# DAPLINK_STLINK_V2-1.net
KiCad netlist of a schematic drawn in Altium Designer
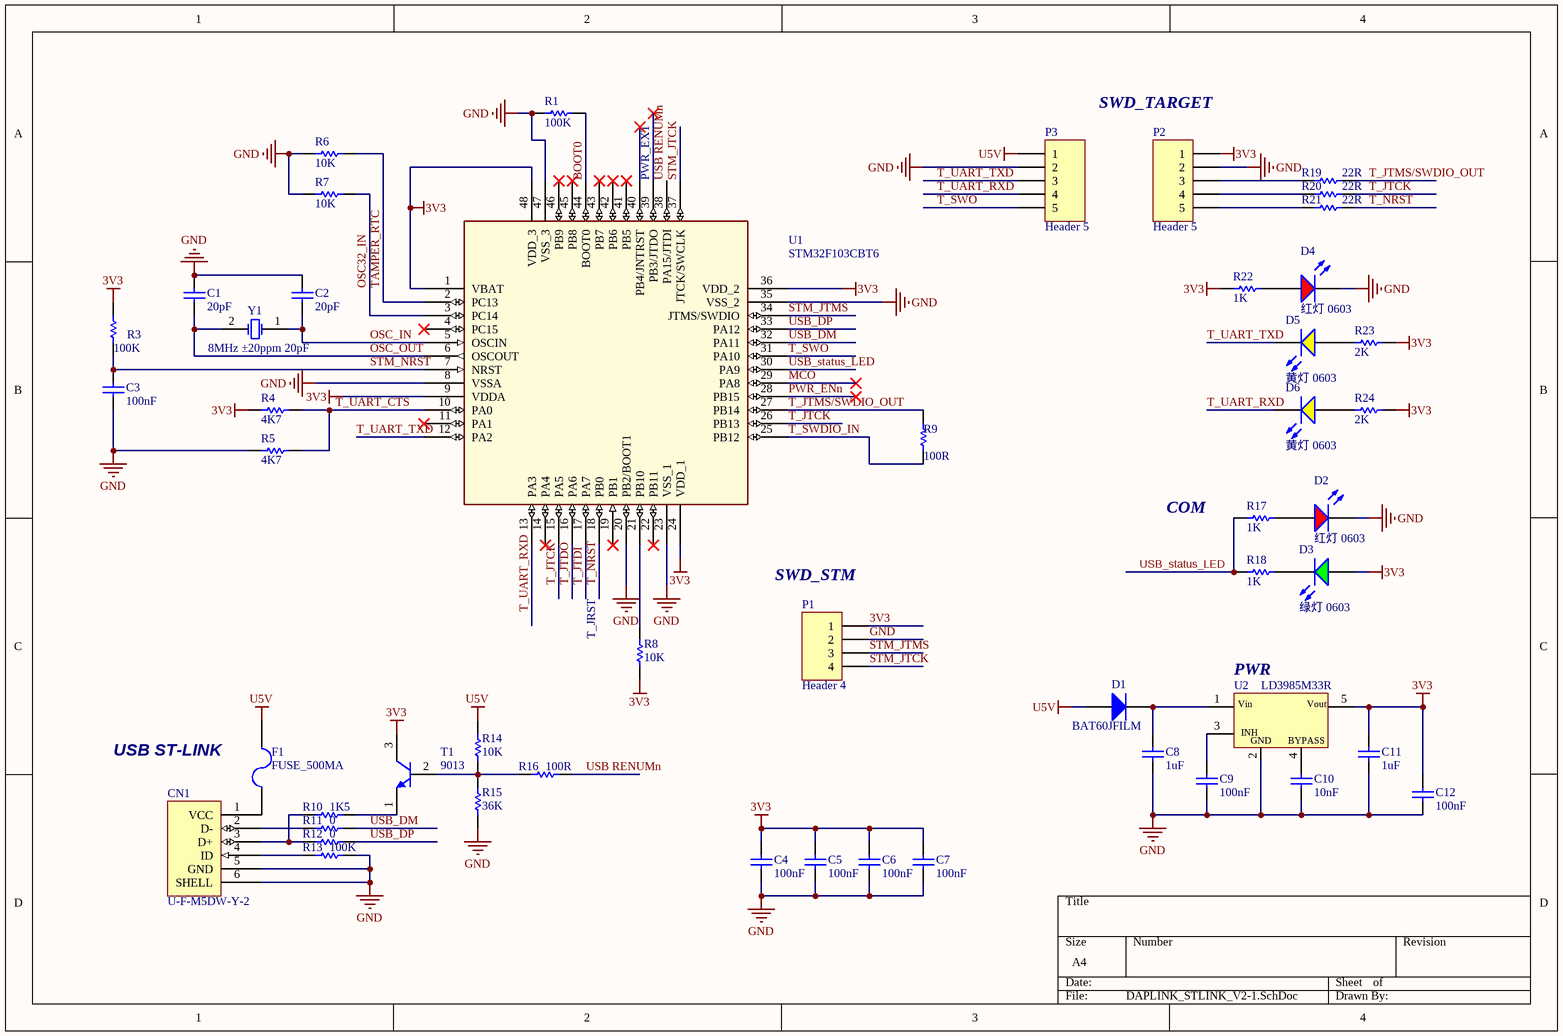
[diagram p0: DAPLINK_STLINK_V2-1.SchDoc]

(export (version "E")
  (design (tool "Eeschema 10.0.6"))
  (components
    (comp (ref "C1")
      (value "20pF")
      (footprint "0603_C")
      (description "Capacitor  0603 20pF")
      (fields (field (name "PUBLISHER") "Altium Limited"))
      (libsource (lib "Miscellaneous Devices") (part "Cap"))
    )
    (comp (ref "C2")
      (value "20pF")
      (footprint "0603_C")
      (description "Capacitor  0603 20pF")
      (fields (field (name "PUBLISHER") "Altium Limited"))
      (libsource (lib "Miscellaneous Devices") (part "Cap"))
    )
    (comp (ref "C3")
      (value "100nF")
      (footprint "0603_C")
      (description "Capacitor  0603 100nF")
      (fields (field (name "PUBLISHER") "Altium Limited"))
      (libsource (lib "Miscellaneous Devices") (part "Cap"))
    )
    (comp (ref "C4")
      (value "100nF")
      (footprint "0603_C")
      (description "Capacitor  0603  100nF")
      (fields (field (name "PUBLISHER") "Altium Limited"))
      (libsource (lib "Miscellaneous Devices") (part "Cap"))
    )
    (comp (ref "C5")
      (value "100nF")
      (footprint "0603_C")
      (description "Capacitor  0603  100nF")
      (fields (field (name "PUBLISHER") "Altium Limited"))
      (libsource (lib "Miscellaneous Devices") (part "Cap"))
    )
    (comp (ref "C6")
      (value "100nF")
      (footprint "0603_C")
      (description "Capacitor 0603 100nF")
      (fields (field (name "PUBLISHER") "Altium Limited"))
      (libsource (lib "Miscellaneous Devices") (part "Cap"))
    )
    (comp (ref "C7")
      (value "100nF")
      (footprint "0603_C")
      (description "Capacitor 0603 100nF")
      (fields (field (name "PUBLISHER") "Altium Limited"))
      (libsource (lib "Miscellaneous Devices") (part "Cap"))
    )
    (comp (ref "C8")
      (value "1uF")
      (footprint "0603_C")
      (description "Capacitor 0603 1uF")
      (fields (field (name "PUBLISHER") "Altium Limited"))
      (libsource (lib "Miscellaneous Devices") (part "Cap"))
    )
    (comp (ref "C9")
      (value "100nF")
      (footprint "0603_C")
      (description "Capacitor 0603 100nF")
      (fields (field (name "PUBLISHER") "Altium Limited"))
      (libsource (lib "Miscellaneous Devices") (part "Cap"))
    )
    (comp (ref "C10")
      (value "10nF")
      (footprint "0603_C")
      (description "Capacitor  0603  10nF")
      (fields (field (name "PUBLISHER") "Altium Limited"))
      (libsource (lib "Miscellaneous Devices") (part "Cap"))
    )
    (comp (ref "C11")
      (value "1uF")
      (footprint "0603_C")
      (description "Capacitor 0603 1uF")
      (fields (field (name "PUBLISHER") "Altium Limited"))
      (libsource (lib "Miscellaneous Devices") (part "Cap"))
    )
    (comp (ref "C12")
      (value "100nF")
      (footprint "0603_C")
      (description "Capacitor  0603  100nF")
      (fields (field (name "PUBLISHER") "Altium Limited"))
      (libsource (lib "Miscellaneous Devices") (part "Cap"))
    )
    (comp (ref "CN1")
      (value "U-F-M5DW-Y-2")
      (footprint "MICRO-USB")
      (description "USB-Micro-typeB connector")
      (libsource (lib "STLINK") (part "USB-MICRO-typeB connector_1"))
    )
    (comp (ref "D1")
      (value "BAT60JFILM")
      (footprint "SOD-323")
      (libsource (lib "STLINK") (part "BAT60JFILM"))
    )
    (comp (ref "D2")
      (value "红灯 0603")
      (footprint "0603_LED_S1")
      (description "发光二极管")
      (libsource (lib "Miscellaneous Devices LC") (part "0603 红灯"))
    )
    (comp (ref "D3")
      (value "绿灯 0603")
      (footprint "0603_LED_S1")
      (description "发光二极管")
      (libsource (lib "Miscellaneous Devices LC") (part "0603 绿灯"))
    )
    (comp (ref "D4")
      (value "红灯 0603")
      (footprint "0603_LED_S1")
      (description "发光二极管")
      (libsource (lib "Miscellaneous Devices LC") (part "0603 红灯"))
    )
    (comp (ref "D5")
      (value "黄灯 0603")
      (footprint "0603_LED_S1")
      (description "发光二极管")
      (libsource (lib "Miscellaneous Devices LC") (part "0603 黄灯"))
    )
    (comp (ref "D6")
      (value "黄灯 0603")
      (footprint "0603_LED_S1")
      (description "发光二极管")
      (libsource (lib "Miscellaneous Devices LC") (part "0603 黄灯"))
    )
    (comp (ref "F1")
      (value "FUSE_500MA")
      (footprint "1206_C")
      (description "自恢复保险丝_SMD1206_500ma")
      (fields (field (name "PUBLISHER") "Altium Limited"))
      (libsource (lib "Miscellaneous Devices") (part "Fuse 2"))
    )
    (comp (ref "P1")
      (value "Header 4")
      (footprint "HDR1X4")
      (description "Header, 4-Pin")
      (fields (field (name "PUBLISHER") "Altium Limited"))
      (libsource (lib "Miscellaneous Connectors") (part "Header 4"))
    )
    (comp (ref "P2")
      (value "Header 5")
      (footprint "HDR2.54-M-WS-5P-2D")
      (description "Header, 5-Pin")
      (fields (field (name "PUBLISHER") "Altium Limited"))
      (libsource (lib "Miscellaneous Connectors") (part "Header 5"))
    )
    (comp (ref "P3")
      (value "Header 5")
      (footprint "HDR2.54-M-WS-5P-2D")
      (description "Header, 5-Pin")
      (fields (field (name "PUBLISHER") "Altium Limited"))
      (libsource (lib "") (part "Header 5_1"))
    )
    (comp (ref "R1")
      (value "100K")
      (footprint "0603_C")
      (description "Resistor 0603")
      (libsource (lib "Miscellaneous Devices") (part "Res1"))
    )
    (comp (ref "R3")
      (value "100K")
      (footprint "0603_C")
      (description "Resistor  0603")
      (libsource (lib "Miscellaneous Devices") (part "Res1"))
    )
    (comp (ref "R4")
      (value "4K7")
      (footprint "0603_C")
      (description "Resistor  0603")
      (libsource (lib "Miscellaneous Devices") (part "Res1"))
    )
    (comp (ref "R5")
      (value "4K7")
      (footprint "0603_C")
      (description "Resistor  0603")
      (libsource (lib "Miscellaneous Devices") (part "Res1"))
    )
    (comp (ref "R6")
      (value "10K")
      (footprint "0603_C")
      (description "Resistor  0603")
      (libsource (lib "Miscellaneous Devices") (part "Res1"))
    )
    (comp (ref "R7")
      (value "10K")
      (footprint "0603_C")
      (description "Resistor  0603")
      (libsource (lib "Miscellaneous Devices") (part "Res1"))
    )
    (comp (ref "R8")
      (value "10K")
      (footprint "0603_C")
      (description "Resistor  0603")
      (libsource (lib "Miscellaneous Devices") (part "Res1"))
    )
    (comp (ref "R9")
      (value "100R")
      (footprint "0603_C")
      (description "Resistor  0603")
      (libsource (lib "Miscellaneous Devices") (part "Res1"))
    )
    (comp (ref "R10")
      (value "1K5")
      (footprint "0603_C")
      (description "Resistor  0603")
      (libsource (lib "Miscellaneous Devices") (part "Res1"))
    )
    (comp (ref "R11")
      (value "0")
      (footprint "0603_C")
      (description "Resistor  0603")
      (libsource (lib "Miscellaneous Devices") (part "Res1"))
    )
    (comp (ref "R12")
      (value "0")
      (footprint "0603_C")
      (description "Resistor  0603")
      (libsource (lib "Miscellaneous Devices") (part "Res1"))
    )
    (comp (ref "R13")
      (value "100K")
      (footprint "0603_C")
      (description "Resistor  0603")
      (libsource (lib "Miscellaneous Devices") (part "Res1"))
    )
    (comp (ref "R14")
      (value "10K")
      (footprint "0603_C")
      (description "Resistor  0603")
      (libsource (lib "Miscellaneous Devices") (part "Res1"))
    )
    (comp (ref "R15")
      (value "36K")
      (footprint "0603_C")
      (description "Resistor  0603")
      (libsource (lib "Miscellaneous Devices") (part "Res1"))
    )
    (comp (ref "R16")
      (value "100R")
      (footprint "0603_C")
      (description "Resistor  0603")
      (libsource (lib "Miscellaneous Devices") (part "Res1"))
    )
    (comp (ref "R17")
      (value "1K")
      (footprint "0603_C")
      (description "Resistor  0603")
      (libsource (lib "Miscellaneous Devices") (part "Res1"))
    )
    (comp (ref "R18")
      (value "1K")
      (footprint "0603_C")
      (description "Resistor  0603")
      (libsource (lib "Miscellaneous Devices") (part "Res1"))
    )
    (comp (ref "R19")
      (value "22R")
      (footprint "0603_C")
      (description "Resistor  0603")
      (libsource (lib "Miscellaneous Devices") (part "Res1"))
    )
    (comp (ref "R20")
      (value "22R")
      (footprint "0603_C")
      (description "Resistor  0603")
      (libsource (lib "Miscellaneous Devices") (part "Res1"))
    )
    (comp (ref "R21")
      (value "22R")
      (footprint "0603_C")
      (description "Resistor  0603")
      (libsource (lib "Miscellaneous Devices") (part "Res1"))
    )
    (comp (ref "R22")
      (value "1K")
      (footprint "0603_C")
      (description "Resistor  0603")
      (libsource (lib "Miscellaneous Devices") (part "Res1"))
    )
    (comp (ref "R23")
      (value "2K")
      (footprint "0603_C")
      (description "Resistor  0603")
      (libsource (lib "Miscellaneous Devices") (part "Res1"))
    )
    (comp (ref "R24")
      (value "2K")
      (footprint "0603_C")
      (description "Resistor  0603")
      (libsource (lib "Miscellaneous Devices") (part "Res1"))
    )
    (comp (ref "T1")
      (value "9013")
      (footprint "SOT-23(SOT-23-3)")
      (description "NPN Bipolar Transistor")
      (fields (field (name "PUBLISHER") "Altium Limited"))
      (libsource (lib "STLINK") (part "NPN"))
    )
    (comp (ref "U1")
      (value "STM32F103CBT6")
      (footprint "LQFP48_0R5_7x7")
      (description "Medium-density performance line ARM-based 32-bit MCU with 128KB Flash")
      (libsource (lib "STLINK") (part "STM32F103CBT6"))
    )
    (comp (ref "U2")
      (value "LD3985M33R")
      (footprint "SOT23-5L")
      (description "Ultra low drop-low noise BiCMOS voltage, regulators low ESR capacitors compatible")
      (libsource (lib "STLINK") (part "LD3985M33R"))
    )
    (comp (ref "Y1")
      (value "8MHz ±20ppm 20pF")
      (footprint "SMD-5032_2P")
      (description "贴片晶振")
      (libsource (lib "Miscellaneous Devices LC") (part "SMD-5032_2P 8MHz 20ppm 20pF"))
    )
  )
  (nets
    (net (code "1") (name "/BOOT0") (class "Default")
      (node (ref "R1") (pin "2") (pinfunction "2_2") (pintype "passive"))
      (node (ref "U1") (pin "44") (pinfunction "BOOT0_44") (pintype "bidirectional"))
    )
    (net (code "2") (name "/MCO") (class "Default")
      (node (ref "U1") (pin "29") (pinfunction "PA8_29") (pintype "bidirectional+no_connect"))
    )
    (net (code "3") (name "/OSC32_IN") (class "Default")
      (node (ref "R7") (pin "1") (pinfunction "1_1") (pintype "passive"))
      (node (ref "U1") (pin "3") (pinfunction "PC14_3") (pintype "bidirectional"))
    )
    (net (code "4") (name "/OSC_IN") (class "Default")
      (node (ref "C2") (pin "1") (pinfunction "1_1") (pintype "passive"))
      (node (ref "U1") (pin "5") (pinfunction "OSCIN_5") (pintype "input"))
      (node (ref "Y1") (pin "1") (pinfunction "OSC1_1") (pintype "passive"))
    )
    (net (code "5") (name "/OSC_OUT") (class "Default")
      (node (ref "C1") (pin "1") (pinfunction "1_1") (pintype "passive"))
      (node (ref "U1") (pin "6") (pinfunction "OSCOUT_6") (pintype "output"))
      (node (ref "Y1") (pin "2") (pinfunction "OSC2_2") (pintype "passive"))
    )
    (net (code "6") (name "/PWR_ENn") (class "Default")
      (node (ref "U1") (pin "28") (pinfunction "PB15_28") (pintype "bidirectional+no_connect"))
    )
    (net (code "7") (name "/STM_JTCK") (class "Default")
      (node (ref "P1") (pin "4") (pinfunction "4_4") (pintype "passive"))
      (node (ref "U1") (pin "37") (pinfunction "JTCK/SWCLK_37") (pintype "bidirectional"))
    )
    (net (code "8") (name "/STM_JTMS") (class "Default")
      (node (ref "P1") (pin "3") (pinfunction "3_3") (pintype "passive"))
      (node (ref "U1") (pin "34") (pinfunction "JTMS/SWDIO_34") (pintype "bidirectional"))
    )
    (net (code "9") (name "/STM_NRST") (class "Default")
      (node (ref "C3") (pin "2") (pinfunction "2_2") (pintype "passive"))
      (node (ref "R3") (pin "1") (pinfunction "1_1") (pintype "passive"))
      (node (ref "U1") (pin "7") (pinfunction "NRST_7") (pintype "input"))
    )
    (net (code "10") (name "/TAMPER_RTC") (class "Default")
      (node (ref "R6") (pin "1") (pinfunction "1_1") (pintype "passive"))
      (node (ref "U1") (pin "2") (pinfunction "PC13_2") (pintype "bidirectional"))
    )
    (net (code "11") (name "/T_JTCK") (class "Default")
      (node (ref "R20") (pin "2") (pinfunction "2_2") (pintype "passive"))
      (node (ref "U1") (pin "15") (pinfunction "PA5_15") (pintype "bidirectional"))
      (node (ref "U1") (pin "26") (pinfunction "PB13_26") (pintype "bidirectional"))
    )
    (net (code "12") (name "/T_JTDI") (class "Default")
      (node (ref "U1") (pin "17") (pinfunction "PA7_17") (pintype "bidirectional"))
    )
    (net (code "13") (name "/T_JTDO") (class "Default")
      (node (ref "U1") (pin "16") (pinfunction "PA6_16") (pintype "bidirectional"))
    )
    (net (code "14") (name "/T_JTMS{slash}SWDIO_OUT") (class "Default")
      (node (ref "R19") (pin "2") (pinfunction "2_2") (pintype "passive"))
      (node (ref "R9") (pin "2") (pinfunction "2_2") (pintype "passive"))
      (node (ref "U1") (pin "27") (pinfunction "PB14_27") (pintype "bidirectional"))
    )
    (net (code "15") (name "/T_NRST") (class "Default")
      (node (ref "R21") (pin "2") (pinfunction "2_2") (pintype "passive"))
      (node (ref "U1") (pin "18") (pinfunction "PB0_18") (pintype "bidirectional"))
    )
    (net (code "16") (name "/T_SWDIO_IN") (class "Default")
      (node (ref "R9") (pin "1") (pinfunction "1_1") (pintype "passive"))
      (node (ref "U1") (pin "25") (pinfunction "PB12_25") (pintype "bidirectional"))
    )
    (net (code "17") (name "/T_SWO") (class "Default")
      (node (ref "P3") (pin "5") (pinfunction "5_5") (pintype "passive"))
      (node (ref "U1") (pin "31") (pinfunction "PA10_31") (pintype "bidirectional"))
    )
    (net (code "18") (name "/T_UART_CTS") (class "Default")
      (node (ref "R4") (pin "1") (pinfunction "1_1") (pintype "passive"))
      (node (ref "R5") (pin "2") (pinfunction "2_2") (pintype "passive"))
      (node (ref "U1") (pin "10") (pinfunction "PA0_10") (pintype "bidirectional"))
    )
    (net (code "19") (name "/T_UART_RXD") (class "Default")
      (node (ref "D6") (pin "K") (pinfunction "K_K") (pintype "passive"))
      (node (ref "P3") (pin "4") (pinfunction "4_4") (pintype "passive"))
      (node (ref "U1") (pin "13") (pinfunction "PA3_13") (pintype "bidirectional"))
    )
    (net (code "20") (name "/T_UART_TXD") (class "Default")
      (node (ref "D5") (pin "K") (pinfunction "K_K") (pintype "passive"))
      (node (ref "P3") (pin "3") (pinfunction "3_3") (pintype "passive"))
      (node (ref "U1") (pin "12") (pinfunction "PA2_12") (pintype "bidirectional"))
    )
    (net (code "21") (name "/USB RENUMn") (class "Default")
      (node (ref "R16") (pin "1") (pinfunction "1_1") (pintype "passive"))
      (node (ref "U1") (pin "38") (pinfunction "PA15/JTDI_38") (pintype "bidirectional"))
    )
    (net (code "22") (name "/USB_DM") (class "Default")
      (node (ref "R11") (pin "1") (pinfunction "1_1") (pintype "passive"))
      (node (ref "U1") (pin "32") (pinfunction "PA11_32") (pintype "bidirectional"))
    )
    (net (code "23") (name "/USB_DP") (class "Default")
      (node (ref "R12") (pin "1") (pinfunction "1_1") (pintype "passive"))
      (node (ref "U1") (pin "33") (pinfunction "PA12_33") (pintype "bidirectional"))
    )
    (net (code "24") (name "/USB_status_LED") (class "Default")
      (node (ref "R17") (pin "1") (pinfunction "1_1") (pintype "passive"))
      (node (ref "R18") (pin "2") (pinfunction "2_2") (pintype "passive"))
      (node (ref "U1") (pin "30") (pinfunction "PA9_30") (pintype "bidirectional"))
    )
    (net (code "25") (name "3V3") (class "Default")
      (node (ref "C11") (pin "1") (pinfunction "1_1") (pintype "passive"))
      (node (ref "C12") (pin "1") (pinfunction "1_1") (pintype "passive"))
      (node (ref "C4") (pin "1") (pinfunction "1_1") (pintype "passive"))
      (node (ref "C5") (pin "1") (pinfunction "1_1") (pintype "passive"))
      (node (ref "C6") (pin "1") (pinfunction "1_1") (pintype "passive"))
      (node (ref "C7") (pin "1") (pinfunction "1_1") (pintype "passive"))
      (node (ref "D3") (pin "A") (pinfunction "A_A") (pintype "passive"))
      (node (ref "P1") (pin "1") (pinfunction "1_1") (pintype "passive"))
      (node (ref "P2") (pin "1") (pinfunction "1_1") (pintype "passive"))
      (node (ref "R22") (pin "1") (pinfunction "1_1") (pintype "passive"))
      (node (ref "R23") (pin "1") (pinfunction "1_1") (pintype "passive"))
      (node (ref "R24") (pin "1") (pinfunction "1_1") (pintype "passive"))
      (node (ref "R3") (pin "2") (pinfunction "2_2") (pintype "passive"))
      (node (ref "R4") (pin "2") (pinfunction "2_2") (pintype "passive"))
      (node (ref "R8") (pin "2") (pinfunction "2_2") (pintype "passive"))
      (node (ref "T1") (pin "3") (pinfunction "C_3") (pintype "passive"))
      (node (ref "U1") (pin "1") (pinfunction "VBAT_1") (pintype "power_in"))
      (node (ref "U1") (pin "24") (pinfunction "VDD_1_24") (pintype "power_in"))
      (node (ref "U1") (pin "36") (pinfunction "VDD_2_36") (pintype "power_in"))
      (node (ref "U1") (pin "48") (pinfunction "VDD_3_48") (pintype "power_in"))
      (node (ref "U1") (pin "9") (pinfunction "VDDA_9") (pintype "power_in"))
      (node (ref "U2") (pin "5") (pinfunction "Vout_5") (pintype "passive"))
    )
    (net (code "26") (name "GND") (class "Default")
      (node (ref "C1") (pin "2") (pinfunction "2_2") (pintype "passive"))
      (node (ref "C10") (pin "2") (pinfunction "2_2") (pintype "passive"))
      (node (ref "C11") (pin "2") (pinfunction "2_2") (pintype "passive"))
      (node (ref "C12") (pin "2") (pinfunction "2_2") (pintype "passive"))
      (node (ref "C2") (pin "2") (pinfunction "2_2") (pintype "passive"))
      (node (ref "C3") (pin "1") (pinfunction "1_1") (pintype "passive"))
      (node (ref "C4") (pin "2") (pinfunction "2_2") (pintype "passive"))
      (node (ref "C5") (pin "2") (pinfunction "2_2") (pintype "passive"))
      (node (ref "C6") (pin "2") (pinfunction "2_2") (pintype "passive"))
      (node (ref "C7") (pin "2") (pinfunction "2_2") (pintype "passive"))
      (node (ref "C8") (pin "2") (pinfunction "2_2") (pintype "passive"))
      (node (ref "C9") (pin "2") (pinfunction "2_2") (pintype "passive"))
      (node (ref "CN1") (pin "5") (pinfunction "GND_5") (pintype "power_in"))
      (node (ref "CN1") (pin "6") (pinfunction "SHELL_6") (pintype "power_in"))
      (node (ref "D2") (pin "K") (pinfunction "K_K") (pintype "passive"))
      (node (ref "D4") (pin "K") (pinfunction "K_K") (pintype "passive"))
      (node (ref "P1") (pin "2") (pinfunction "2_2") (pintype "passive"))
      (node (ref "P2") (pin "2") (pinfunction "2_2") (pintype "passive"))
      (node (ref "P3") (pin "2") (pinfunction "2_2") (pintype "passive"))
      (node (ref "R1") (pin "1") (pinfunction "1_1") (pintype "passive"))
      (node (ref "R13") (pin "1") (pinfunction "1_1") (pintype "passive"))
      (node (ref "R15") (pin "2") (pinfunction "2_2") (pintype "passive"))
      (node (ref "R5") (pin "1") (pinfunction "1_1") (pintype "passive"))
      (node (ref "R6") (pin "2") (pinfunction "2_2") (pintype "passive"))
      (node (ref "R7") (pin "2") (pinfunction "2_2") (pintype "passive"))
      (node (ref "U1") (pin "20") (pinfunction "PB2/BOOT1_20") (pintype "bidirectional"))
      (node (ref "U1") (pin "23") (pinfunction "VSS_1_23") (pintype "power_in"))
      (node (ref "U1") (pin "35") (pinfunction "VSS_2_35") (pintype "power_in"))
      (node (ref "U1") (pin "47") (pinfunction "VSS_3_47") (pintype "power_in"))
      (node (ref "U1") (pin "8") (pinfunction "VSSA_8") (pintype "power_in"))
      (node (ref "U2") (pin "2") (pinfunction "GND_2") (pintype "passive"))
    )
    (net (code "27") (name "Net-(CN1-D+)") (class "Default")
      (node (ref "CN1") (pin "3") (pinfunction "D+_3") (pintype "bidirectional"))
      (node (ref "R10") (pin "2") (pinfunction "2_2") (pintype "passive"))
      (node (ref "R12") (pin "2") (pinfunction "2_2") (pintype "passive"))
    )
    (net (code "28") (name "Net-(CN1-D-)") (class "Default")
      (node (ref "CN1") (pin "2") (pinfunction "D-_2") (pintype "bidirectional"))
      (node (ref "R11") (pin "2") (pinfunction "2_2") (pintype "passive"))
    )
    (net (code "29") (name "Net-(CN1-ID)") (class "Default")
      (node (ref "CN1") (pin "4") (pinfunction "ID_4") (pintype "input"))
      (node (ref "R13") (pin "2") (pinfunction "2_2") (pintype "passive"))
    )
    (net (code "30") (name "Net-(CN1-VCC)") (class "Default")
      (node (ref "CN1") (pin "1") (pinfunction "VCC_1") (pintype "power_in"))
      (node (ref "F1") (pin "1") (pinfunction "1_1") (pintype "passive"))
    )
    (net (code "31") (name "Net-(D1-K)") (class "Default")
      (node (ref "C8") (pin "1") (pinfunction "1_1") (pintype "passive"))
      (node (ref "D1") (pin "2") (pinfunction "K_2") (pintype "passive"))
      (node (ref "U2") (pin "1") (pinfunction "Vin_1") (pintype "passive"))
    )
    (net (code "32") (name "Net-(D2-PadA)") (class "Default")
      (node (ref "D2") (pin "A") (pinfunction "A_A") (pintype "passive"))
      (node (ref "R17") (pin "2") (pinfunction "2_2") (pintype "passive"))
    )
    (net (code "33") (name "Net-(D3-PadK)") (class "Default")
      (node (ref "D3") (pin "K") (pinfunction "K_K") (pintype "passive"))
      (node (ref "R18") (pin "1") (pinfunction "1_1") (pintype "passive"))
    )
    (net (code "34") (name "Net-(D4-PadA)") (class "Default")
      (node (ref "D4") (pin "A") (pinfunction "A_A") (pintype "passive"))
      (node (ref "R22") (pin "2") (pinfunction "2_2") (pintype "passive"))
    )
    (net (code "35") (name "Net-(D5-PadA)") (class "Default")
      (node (ref "D5") (pin "A") (pinfunction "A_A") (pintype "passive"))
      (node (ref "R23") (pin "2") (pinfunction "2_2") (pintype "passive"))
    )
    (net (code "36") (name "Net-(D6-PadA)") (class "Default")
      (node (ref "D6") (pin "A") (pinfunction "A_A") (pintype "passive"))
      (node (ref "R24") (pin "2") (pinfunction "2_2") (pintype "passive"))
    )
    (net (code "37") (name "Net-(P2-Pad3)") (class "Default")
      (node (ref "P2") (pin "3") (pinfunction "3_3") (pintype "passive"))
      (node (ref "R19") (pin "1") (pinfunction "1_1") (pintype "passive"))
    )
    (net (code "38") (name "Net-(P2-Pad4)") (class "Default")
      (node (ref "P2") (pin "4") (pinfunction "4_4") (pintype "passive"))
      (node (ref "R20") (pin "1") (pinfunction "1_1") (pintype "passive"))
    )
    (net (code "39") (name "Net-(P2-Pad5)") (class "Default")
      (node (ref "P2") (pin "5") (pinfunction "5_5") (pintype "passive"))
      (node (ref "R21") (pin "1") (pinfunction "1_1") (pintype "passive"))
    )
    (net (code "40") (name "Net-(T1-B)") (class "Default")
      (node (ref "R14") (pin "2") (pinfunction "2_2") (pintype "passive"))
      (node (ref "R15") (pin "1") (pinfunction "1_1") (pintype "passive"))
      (node (ref "R16") (pin "2") (pinfunction "2_2") (pintype "passive"))
      (node (ref "T1") (pin "2") (pinfunction "B_2") (pintype "passive"))
    )
    (net (code "41") (name "Net-(T1-E)") (class "Default")
      (node (ref "R10") (pin "1") (pinfunction "1_1") (pintype "passive"))
      (node (ref "T1") (pin "1") (pinfunction "E_1") (pintype "passive"))
    )
    (net (code "42") (name "Net-(U1-PB10)") (class "Default")
      (node (ref "R8") (pin "1") (pinfunction "1_1") (pintype "passive"))
      (node (ref "U1") (pin "21") (pinfunction "PB10_21") (pintype "bidirectional"))
    )
    (net (code "43") (name "Net-(U2-BYPASS)") (class "Default")
      (node (ref "C10") (pin "1") (pinfunction "1_1") (pintype "passive"))
      (node (ref "U2") (pin "4") (pinfunction "BYPASS_4") (pintype "passive"))
    )
    (net (code "44") (name "Net-(U2-CE)") (class "Default")
      (node (ref "C9") (pin "1") (pinfunction "1_1") (pintype "passive"))
      (node (ref "U2") (pin "3") (pinfunction "CE_3") (pintype "passive"))
    )
    (net (code "45") (name "U5V") (class "Default")
      (node (ref "D1") (pin "1") (pinfunction "A_1") (pintype "passive"))
      (node (ref "F1") (pin "2") (pinfunction "2_2") (pintype "passive"))
      (node (ref "P3") (pin "1") (pinfunction "1_1") (pintype "passive"))
      (node (ref "R14") (pin "1") (pinfunction "1_1") (pintype "passive"))
    )
    (net (code "46") (name "unconnected-(U1-PA1-Pad11)") (class "Default")
      (node (ref "U1") (pin "11") (pinfunction "PA1_11") (pintype "bidirectional+no_connect"))
    )
    (net (code "47") (name "unconnected-(U1-PA4-Pad14)") (class "Default")
      (node (ref "U1") (pin "14") (pinfunction "PA4_14") (pintype "bidirectional+no_connect"))
    )
    (net (code "48") (name "unconnected-(U1-PB1-Pad19)") (class "Default")
      (node (ref "U1") (pin "19") (pinfunction "PB1_19") (pintype "input+no_connect"))
    )
    (net (code "49") (name "unconnected-(U1-PB3{slash}JTDO-Pad39)") (class "Default")
      (node (ref "U1") (pin "39") (pinfunction "PB3/JTDO_39") (pintype "bidirectional+no_connect"))
    )
    (net (code "50") (name "unconnected-(U1-PB4{slash}JNTRST-Pad40)") (class "Default")
      (node (ref "U1") (pin "40") (pinfunction "PB4/JNTRST_40") (pintype "bidirectional+no_connect"))
    )
    (net (code "51") (name "unconnected-(U1-PB5-Pad41)") (class "Default")
      (node (ref "U1") (pin "41") (pinfunction "PB5_41") (pintype "bidirectional+no_connect"))
    )
    (net (code "52") (name "unconnected-(U1-PB6-Pad42)") (class "Default")
      (node (ref "U1") (pin "42") (pinfunction "PB6_42") (pintype "bidirectional+no_connect"))
    )
    (net (code "53") (name "unconnected-(U1-PB7-Pad43)") (class "Default")
      (node (ref "U1") (pin "43") (pinfunction "PB7_43") (pintype "bidirectional+no_connect"))
    )
    (net (code "54") (name "unconnected-(U1-PB8-Pad45)") (class "Default")
      (node (ref "U1") (pin "45") (pinfunction "PB8_45") (pintype "bidirectional+no_connect"))
    )
    (net (code "55") (name "unconnected-(U1-PB9-Pad46)") (class "Default")
      (node (ref "U1") (pin "46") (pinfunction "PB9_46") (pintype "bidirectional+no_connect"))
    )
    (net (code "56") (name "unconnected-(U1-PB11-Pad22)") (class "Default")
      (node (ref "U1") (pin "22") (pinfunction "PB11_22") (pintype "bidirectional+no_connect"))
    )
    (net (code "57") (name "unconnected-(U1-PC15-Pad4)") (class "Default")
      (node (ref "U1") (pin "4") (pinfunction "PC15_4") (pintype "bidirectional+no_connect"))
    )
  )
)
